# V1.net
KiCad netlist of a schematic drawn in Altium Designer
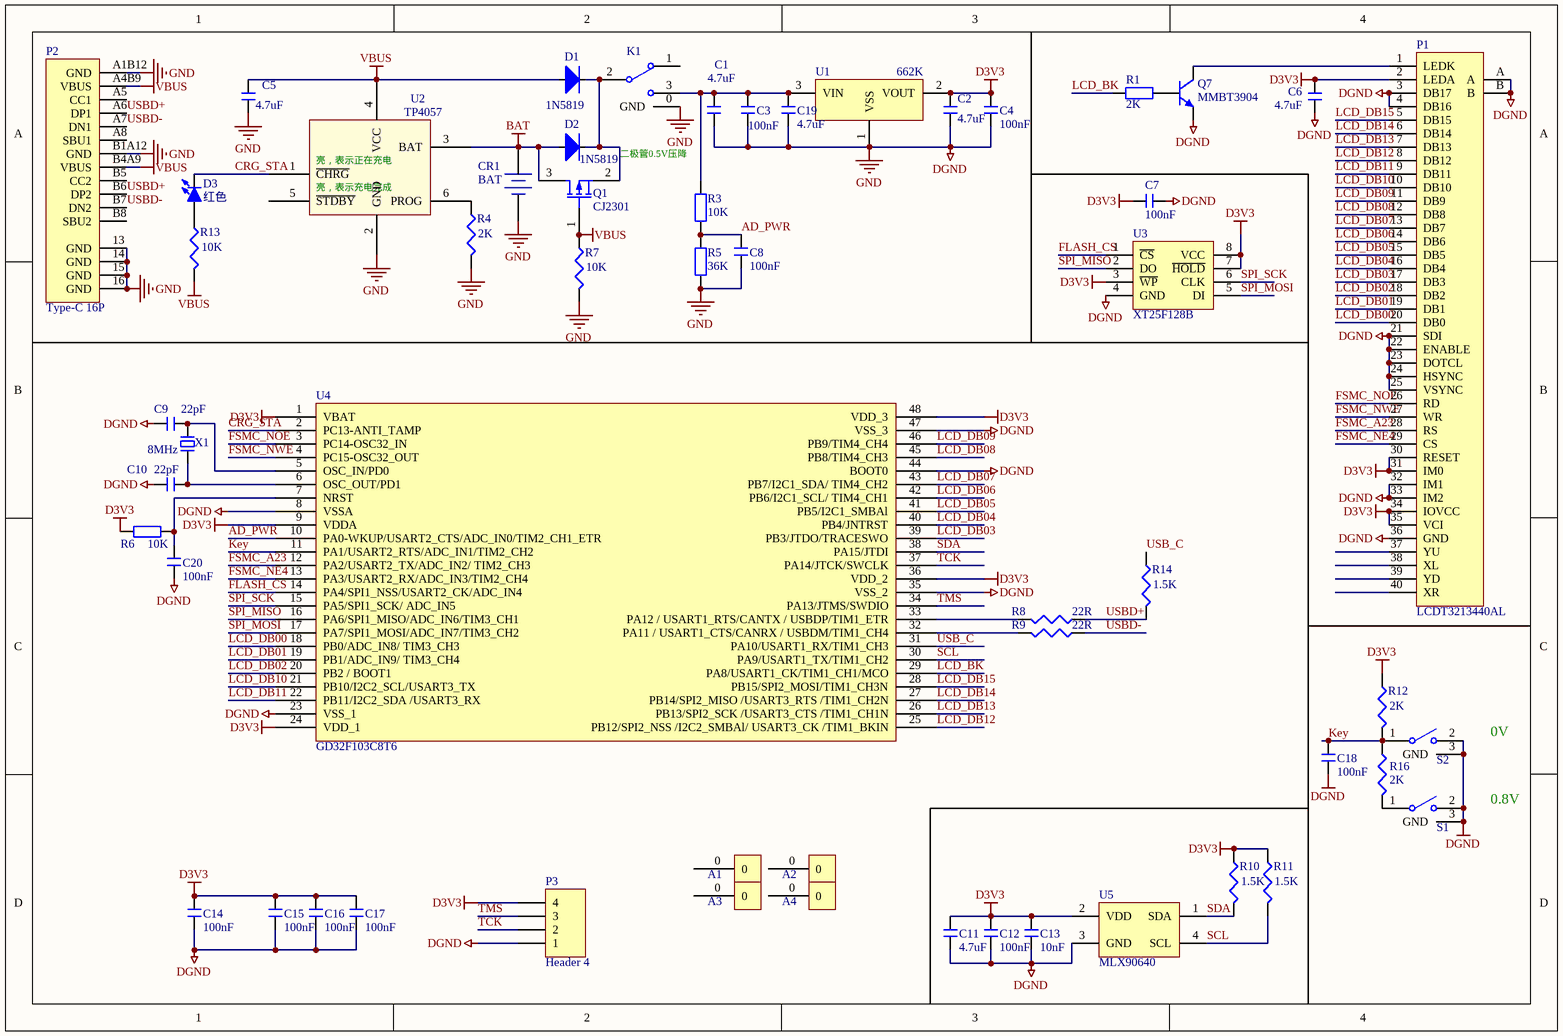
[diagram p0: 红外热成像V1.SchDoc]

(export (version "E")
  (design (tool "Eeschema 10.0.6"))
  (components
    (comp (ref "A1") (value "安装孔") (footprint "安装孔") (libsource (lib "standard") (part "安装孔")))
    (comp (ref "A2") (value "安装孔") (footprint "安装孔") (libsource (lib "standard") (part "安装孔")))
    (comp (ref "A3") (value "安装孔") (footprint "安装孔") (libsource (lib "standard") (part "安装孔")))
    (comp (ref "A4") (value "安装孔") (footprint "安装孔") (libsource (lib "standard") (part "安装孔")))
    (comp (ref "C1")
      (value "4.7uF")
      (footprint "C0603")
      (description "CAP")
      (fields (field (name "版权归属") "源创客"))
      (libsource (lib "3.1   - 电阻-电容-电感") (part "C"))
    )
    (comp (ref "C2")
      (value "4.7uF")
      (footprint "C0603")
      (description "CAP")
      (fields (field (name "版权归属") "源创客"))
      (libsource (lib "3.1   - 电阻-电容-电感") (part "C"))
    )
    (comp (ref "C3")
      (value "100nF")
      (footprint "C0603")
      (description "CAP")
      (fields (field (name "版权归属") "源创客"))
      (libsource (lib "3.1   - 电阻-电容-电感") (part "C"))
    )
    (comp (ref "C4")
      (value "100nF")
      (footprint "C0603")
      (description "CAP")
      (fields (field (name "版权归属") "源创客"))
      (libsource (lib "3.1   - 电阻-电容-电感") (part "C"))
    )
    (comp (ref "C5")
      (value "4.7uF")
      (footprint "C0603")
      (description "CAP")
      (fields (field (name "版权归属") "源创客"))
      (libsource (lib "3.1   - 电阻-电容-电感") (part "C"))
    )
    (comp (ref "C6")
      (value "4.7uF")
      (footprint "C0603")
      (description "CAP")
      (fields (field (name "版权归属") "源创客"))
      (libsource (lib "3.1   - 电阻-电容-电感") (part "C"))
    )
    (comp (ref "C7")
      (value "100nF")
      (footprint "C0603")
      (description "CAP")
      (fields (field (name "版权归属") "源创客"))
      (libsource (lib "3.1   - 电阻-电容-电感") (part "C"))
    )
    (comp (ref "C8")
      (value "100nF")
      (footprint "C0603")
      (description "CAP")
      (fields (field (name "版权归属") "源创客"))
      (libsource (lib "3.1   - 电阻-电容-电感") (part "C"))
    )
    (comp (ref "C9")
      (value "22pF")
      (footprint "C0603")
      (description "CAP")
      (fields (field (name "版权归属") "源创客"))
      (libsource (lib "3.1   - 电阻-电容-电感") (part "C"))
    )
    (comp (ref "C10")
      (value "22pF")
      (footprint "C0603")
      (description "CAP")
      (fields (field (name "版权归属") "源创客"))
      (libsource (lib "3.1   - 电阻-电容-电感") (part "C"))
    )
    (comp (ref "C11")
      (value "4.7uF")
      (footprint "C0603")
      (description "CAP")
      (fields (field (name "版权归属") "源创客"))
      (libsource (lib "3.1   - 电阻-电容-电感") (part "C"))
    )
    (comp (ref "C12")
      (value "100nF")
      (footprint "C0603")
      (description "CAP")
      (fields (field (name "版权归属") "源创客"))
      (libsource (lib "3.1   - 电阻-电容-电感") (part "C"))
    )
    (comp (ref "C13")
      (value "10nF")
      (footprint "C0603")
      (description "CAP")
      (fields (field (name "版权归属") "源创客"))
      (libsource (lib "3.1   - 电阻-电容-电感") (part "C"))
    )
    (comp (ref "C14")
      (value "100nF")
      (footprint "C0603")
      (description "CAP")
      (fields (field (name "版权归属") "源创客"))
      (libsource (lib "3.1   - 电阻-电容-电感") (part "C"))
    )
    (comp (ref "C15")
      (value "100nF")
      (footprint "C0603")
      (description "CAP")
      (fields (field (name "版权归属") "源创客"))
      (libsource (lib "3.1   - 电阻-电容-电感") (part "C"))
    )
    (comp (ref "C16")
      (value "100nF")
      (footprint "C0603")
      (description "CAP")
      (fields (field (name "版权归属") "源创客"))
      (libsource (lib "3.1   - 电阻-电容-电感") (part "C"))
    )
    (comp (ref "C17")
      (value "100nF")
      (footprint "C0603")
      (description "CAP")
      (fields (field (name "版权归属") "源创客"))
      (libsource (lib "3.1   - 电阻-电容-电感") (part "C"))
    )
    (comp (ref "C18")
      (value "100nF")
      (footprint "C0603")
      (description "CAP")
      (fields (field (name "版权归属") "源创客"))
      (libsource (lib "3.1   - 电阻-电容-电感") (part "C"))
    )
    (comp (ref "C19")
      (value "4.7uF")
      (footprint "C0603")
      (description "CAP")
      (fields (field (name "版权归属") "源创客"))
      (libsource (lib "3.1   - 电阻-电容-电感") (part "C"))
    )
    (comp (ref "C20")
      (value "100nF")
      (footprint "C0603")
      (description "CAP")
      (fields (field (name "版权归属") "源创客"))
      (libsource (lib "3.1   - 电阻-电容-电感") (part "C"))
    )
    (comp (ref "CR1")
      (value "BAT")
      (footprint "BAT")
      (description "锂电池")
      (fields (field (name "版权归属") "源创客"))
      (libsource (lib "未分类器件") (part "CR-3V"))
    )
    (comp (ref "D1")
      (value "1N5819")
      (footprint "SOD123")
      (description "二极管_整流")
      (fields (field (name "PUBLISHER") "Altium Limited"))
      (libsource (lib "*") (part "Diode"))
    )
    (comp (ref "D2")
      (value "1N5819")
      (footprint "SOD123")
      (description "二极管_整流")
      (fields (field (name "PUBLISHER") "Altium Limited"))
      (libsource (lib "*") (part "Diode"))
    )
    (comp (ref "D3")
      (value "红色")
      (footprint "D0805")
      (description "贴片LED")
      (fields (field (name "版权归属") "源创客"))
      (libsource (lib "9.1   - LED") (part "LED-SMD"))
    )
    (comp (ref "K1")
      (value "SS-12F23")
      (footprint "3P SW")
      (description "开关")
      (fields (field (name "版权归属") "源创客"))
      (libsource (lib "Schlib1") (part "SSW-1P"))
    )
    (comp (ref "P1")
      (value "LCDT3213440AL")
      (footprint "LCDT3213440AL")
      (description "接插件")
      (libsource (lib "Power_Show - V4") (part "LCDT3213440AL"))
    )
    (comp (ref "P2")
      (value "Type-C 16P")
      (footprint "Type-C 16P")
      (description "接插件")
      (libsource (lib "Schlib1") (part "Type-C 16P"))
    )
    (comp (ref "P3")
      (value "Header 4")
      (footprint "4PIN-1.27-STLink")
      (description "Header, 4-Pin")
      (fields (field (name "PUBLISHER") "Altium Limited"))
      (libsource (lib "Miscellaneous Connectors") (part "Header 4"))
    )
    (comp (ref "Q1")
      (value "CJ2301")
      (footprint "SOT-23")
      (description "MOS")
      (fields (field (name "PUBLISHER") "Altium Limited"))
      (libsource (lib "Miscellaneous Devices") (part "MOSFET-P"))
    )
    (comp (ref "Q7")
      (value "MMBT3904")
      (footprint "SOT23-3L")
      (description "三极管")
      (fields (field (name "版权归属") "源创客"))
      (libsource (lib "三极管") (part "9013-SMD"))
    )
    (comp (ref "R1")
      (value "2K")
      (footprint "R0603")
      (description "RES")
      (libsource (lib "standard") (part "RSSR0603"))
    )
    (comp (ref "R3")
      (value "10K")
      (footprint "R0603")
      (description "RES")
      (fields (field (name "版权归属") "源创客"))
      (libsource (lib "3.1   - 电阻-电容-电感") (part "R-Precision"))
    )
    (comp (ref "R4") (value "2K") (footprint "R0603") (description "RES") (libsource (lib "*") (part "RES")))
    (comp (ref "R5")
      (value "36K")
      (footprint "R0603")
      (description "RES")
      (fields (field (name "版权归属") "源创客"))
      (libsource (lib "3.1   - 电阻-电容-电感") (part "R-Precision"))
    )
    (comp (ref "R6")
      (value "10K")
      (footprint "R0603")
      (description "RES")
      (fields (field (name "版权归属") "源创客"))
      (libsource (lib "3.1   - 电阻-电容-电感") (part "R-Precision"))
    )
    (comp (ref "R7") (value "10K") (footprint "R0603") (description "RES") (libsource (lib "*") (part "RES")))
    (comp (ref "R8") (value "22R") (footprint "R0603") (description "RES") (libsource (lib "*") (part "RES")))
    (comp (ref "R9") (value "22R") (footprint "R0603") (description "RES") (libsource (lib "*") (part "RES")))
    (comp (ref "R10")
      (value "1.5K")
      (footprint "R0603")
      (description "RES")
      (libsource (lib "*") (part "RES"))
    )
    (comp (ref "R11")
      (value "1.5K")
      (footprint "R0603")
      (description "RES")
      (libsource (lib "*") (part "RES"))
    )
    (comp (ref "R12") (value "2K") (footprint "R0603") (description "RES") (libsource (lib "*") (part "RES")))
    (comp (ref "R13")
      (value "10K")
      (footprint "R0603")
      (description "RES")
      (libsource (lib "*") (part "RES"))
    )
    (comp (ref "R14")
      (value "1.5K")
      (footprint "R0603")
      (description "RES")
      (libsource (lib "*") (part "RES"))
    )
    (comp (ref "R16") (value "2K") (footprint "R0603") (description "RES") (libsource (lib "*") (part "RES")))
    (comp (ref "S1")
      (value "KCD1-101")
      (footprint "3P-Key")
      (description "按键")
      (fields (field (name "版权归属") "源创客"))
      (libsource (lib "Schlib1") (part "KCD1-101"))
    )
    (comp (ref "S2")
      (value "KCD1-101")
      (footprint "3P-Key")
      (description "按键")
      (fields (field (name "版权归属") "源创客"))
      (libsource (lib "Schlib1") (part "KCD1-101"))
    )
    (comp (ref "U1")
      (value "662K")
      (footprint "SOT-23")
      (description "芯片")
      (libsource (lib "Schlib1") (part "662K"))
    )
    (comp (ref "U2")
      (value "TP4057")
      (footprint "SOT23-6")
      (description "芯片")
      (libsource (lib "GBRL_Show") (part "Component_1"))
    )
    (comp (ref "U3")
      (value "XT25F128B")
      (footprint "SOP8W_N")
      (description "芯片")
      (fields (field (name "版权归属") "源创客"))
      (libsource (lib "IC芯片") (part "W25Qxx"))
    )
    (comp (ref "U4")
      (value "GD32F103C8T6")
      (footprint "LQFP_48")
      (description "芯片")
      (libsource (lib "*") (part "STM32F103CX"))
    )
    (comp (ref "U5")
      (value "MLX90640")
      (footprint "MLX90640")
      (description "芯片")
      (libsource (lib "Schlib1") (part "MLX90460"))
    )
    (comp (ref "X1")
      (value "8MHz")
      (footprint "XSR - duplicate")
      (description "晶振")
      (fields (field (name "版权归属") "源创客"))
      (libsource (lib "10.1 - 保险丝-晶振") (part "XTAL-2P"))
    )
  )
  (nets
    (net (code "1") (name "/AD_PWR") (class "Default")
      (node (ref "C8") (pin "2") (pinfunction "2_2") (pintype "passive"))
      (node (ref "R3") (pin "1") (pinfunction "1_1") (pintype "passive"))
      (node (ref "R5") (pin "2") (pinfunction "2_2") (pintype "passive"))
      (node (ref "U4") (pin "10") (pinfunction "PA0-WKUP/USART2_CTS/ADC_IN0/TIM2_CH1_ETR_10") (pintype "passive"))
    )
    (net (code "2") (name "/CRG_STA") (class "Default")
      (node (ref "D3") (pin "2") (pinfunction "K_2") (pintype "passive"))
      (node (ref "U2") (pin "1") (pinfunction "~{CHRG}_1") (pintype "passive"))
      (node (ref "U4") (pin "2") (pinfunction "PC13-ANTI_TAMP_2") (pintype "passive"))
    )
    (net (code "3") (name "/FLASH_CS") (class "Default")
      (node (ref "U3") (pin "1") (pinfunction "~{CS}_1") (pintype "passive"))
      (node (ref "U4") (pin "14") (pinfunction "PA4/SPI1_NSS/USART2_CK/ADC_IN4_14") (pintype "passive"))
    )
    (net (code "4") (name "/FSMC_A23") (class "Default")
      (node (ref "P1") (pin "28") (pinfunction "RS_28") (pintype "passive"))
      (node (ref "U4") (pin "12") (pinfunction "PA2/USART2_TX/ADC_IN2/_TIM2_CH3_12") (pintype "passive"))
    )
    (net (code "5") (name "/FSMC_NE4") (class "Default")
      (node (ref "P1") (pin "29") (pinfunction "CS_29") (pintype "passive"))
      (node (ref "U4") (pin "13") (pinfunction "PA3/USART2_RX/ADC_IN3/TIM2_CH4_13") (pintype "passive"))
    )
    (net (code "6") (name "/FSMC_NOE") (class "Default")
      (node (ref "P1") (pin "26") (pinfunction "RD_26") (pintype "passive"))
      (node (ref "U4") (pin "3") (pinfunction "PC14-OSC32_IN_3") (pintype "passive"))
    )
    (net (code "7") (name "/FSMC_NWE") (class "Default")
      (node (ref "P1") (pin "27") (pinfunction "WR_27") (pintype "passive"))
      (node (ref "U4") (pin "4") (pinfunction "PC15-OSC32_OUT_4") (pintype "passive"))
    )
    (net (code "8") (name "/Key") (class "Default")
      (node (ref "C18") (pin "2") (pinfunction "2_2") (pintype "passive"))
      (node (ref "R12") (pin "1") (pintype "passive"))
      (node (ref "R16") (pin "2") (pintype "passive"))
      (node (ref "S2") (pin "1") (pinfunction "1_1") (pintype "passive"))
      (node (ref "U4") (pin "11") (pinfunction "PA1/USART2_RTS/ADC_IN1/TIM2_CH2_11") (pintype "passive"))
    )
    (net (code "9") (name "/LCD_BK") (class "Default")
      (node (ref "R1") (pin "2") (pinfunction "2_2") (pintype "passive"))
      (node (ref "U4") (pin "29") (pinfunction "PA8/USART1_CK/TIM1_CH1/MCO_29") (pintype "passive"))
    )
    (net (code "10") (name "/LCD_DB00") (class "Default")
      (node (ref "P1") (pin "20") (pinfunction "DB0_20") (pintype "passive"))
      (node (ref "U4") (pin "18") (pinfunction "PB0/ADC_IN8/_TIM3_CH3_18") (pintype "passive"))
    )
    (net (code "11") (name "/LCD_DB01") (class "Default")
      (node (ref "P1") (pin "19") (pinfunction "DB1_19") (pintype "passive"))
      (node (ref "U4") (pin "19") (pinfunction "PB1/ADC_IN9/_TIM3_CH4_19") (pintype "passive"))
    )
    (net (code "12") (name "/LCD_DB02") (class "Default")
      (node (ref "P1") (pin "18") (pinfunction "DB2_18") (pintype "passive"))
      (node (ref "U4") (pin "20") (pinfunction "PB2_/_BOOT1_20") (pintype "passive"))
    )
    (net (code "13") (name "/LCD_DB03") (class "Default")
      (node (ref "P1") (pin "17") (pinfunction "DB3_17") (pintype "passive"))
      (node (ref "U4") (pin "39") (pinfunction "PB3/JTDO/TRACESWO_39") (pintype "passive"))
    )
    (net (code "14") (name "/LCD_DB04") (class "Default")
      (node (ref "P1") (pin "16") (pinfunction "DB4_16") (pintype "passive"))
      (node (ref "U4") (pin "40") (pinfunction "PB4/JNTRST_40") (pintype "passive"))
    )
    (net (code "15") (name "/LCD_DB05") (class "Default")
      (node (ref "P1") (pin "15") (pinfunction "DB5_15") (pintype "passive"))
      (node (ref "U4") (pin "41") (pinfunction "PB5/I2C1_SMBAl_41") (pintype "passive"))
    )
    (net (code "16") (name "/LCD_DB06") (class "Default")
      (node (ref "P1") (pin "14") (pinfunction "DB6_14") (pintype "passive"))
      (node (ref "U4") (pin "42") (pinfunction "PB6/I2C1_SCL/_TIM4_CH1_42") (pintype "passive"))
    )
    (net (code "17") (name "/LCD_DB07") (class "Default")
      (node (ref "P1") (pin "13") (pinfunction "DB7_13") (pintype "passive"))
      (node (ref "U4") (pin "43") (pinfunction "PB7/I2C1_SDA/_TIM4_CH2_43") (pintype "passive"))
    )
    (net (code "18") (name "/LCD_DB08") (class "Default")
      (node (ref "P1") (pin "12") (pinfunction "DB8_12") (pintype "passive"))
      (node (ref "U4") (pin "45") (pinfunction "PB8/TIM4_CH3_45") (pintype "passive"))
    )
    (net (code "19") (name "/LCD_DB09") (class "Default")
      (node (ref "P1") (pin "11") (pinfunction "DB9_11") (pintype "passive"))
      (node (ref "U4") (pin "46") (pinfunction "PB9/TIM4_CH4_46") (pintype "passive"))
    )
    (net (code "20") (name "/LCD_DB10") (class "Default")
      (node (ref "P1") (pin "10") (pinfunction "DB10_10") (pintype "passive"))
      (node (ref "U4") (pin "21") (pinfunction "PB10/I2C2_SCL/USART3_TX_21") (pintype "passive"))
    )
    (net (code "21") (name "/LCD_DB11") (class "Default")
      (node (ref "P1") (pin "9") (pinfunction "DB11_9") (pintype "passive"))
      (node (ref "U4") (pin "22") (pinfunction "PB11/I2C2_SDA_/USART3_RX_22") (pintype "passive"))
    )
    (net (code "22") (name "/LCD_DB12") (class "Default")
      (node (ref "P1") (pin "8") (pinfunction "DB12_8") (pintype "passive"))
      (node (ref "U4") (pin "25") (pinfunction "PB12/SPI2_NSS_/I2C2_SMBAl/_USART3_CK_/TIM1_BKIN_25") (pintype "passive"))
    )
    (net (code "23") (name "/LCD_DB13") (class "Default")
      (node (ref "P1") (pin "7") (pinfunction "DB13_7") (pintype "passive"))
      (node (ref "U4") (pin "26") (pinfunction "PB13/SPI2_SCK_/USART3_CTS_/TIM1_CH1N_26") (pintype "passive"))
    )
    (net (code "24") (name "/LCD_DB14") (class "Default")
      (node (ref "P1") (pin "6") (pinfunction "DB14_6") (pintype "passive"))
      (node (ref "U4") (pin "27") (pinfunction "PB14/SPI2_MISO_/USART3_RTS_/TIM1_CH2N_27") (pintype "passive"))
    )
    (net (code "25") (name "/LCD_DB15") (class "Default")
      (node (ref "P1") (pin "5") (pinfunction "DB15_5") (pintype "passive"))
      (node (ref "U4") (pin "28") (pinfunction "PB15/SPI2_MOSI/TIM1_CH3N_28") (pintype "passive"))
    )
    (net (code "26") (name "/SCL") (class "Default")
      (node (ref "R11") (pin "1") (pintype "passive"))
      (node (ref "U4") (pin "30") (pinfunction "PA9/USART1_TX/TIM1_CH2_30") (pintype "passive"))
      (node (ref "U5") (pin "4") (pinfunction "SCL_4") (pintype "passive"))
    )
    (net (code "27") (name "/SDA") (class "Default")
      (node (ref "R10") (pin "1") (pintype "passive"))
      (node (ref "U4") (pin "38") (pinfunction "PA15/JTDI_38") (pintype "passive"))
      (node (ref "U5") (pin "1") (pinfunction "SDA_1") (pintype "passive"))
    )
    (net (code "28") (name "/SPI_MISO") (class "Default")
      (node (ref "U3") (pin "2") (pinfunction "DO_2") (pintype "passive"))
      (node (ref "U4") (pin "16") (pinfunction "PA6/SPI1_MISO/ADC_IN6/TIM3_CH1_16") (pintype "passive"))
    )
    (net (code "29") (name "/SPI_MOSI") (class "Default")
      (node (ref "U3") (pin "5") (pinfunction "DI_5") (pintype "passive"))
      (node (ref "U4") (pin "17") (pinfunction "PA7/SPI1_MOSI/ADC_IN7/TIM3_CH2_17") (pintype "passive"))
    )
    (net (code "30") (name "/SPI_SCK") (class "Default")
      (node (ref "U3") (pin "6") (pinfunction "CLK_6") (pintype "passive"))
      (node (ref "U4") (pin "15") (pinfunction "PA5/SPI1_SCK/_ADC_IN5_15") (pintype "passive"))
    )
    (net (code "31") (name "/TCK") (class "Default")
      (node (ref "P3") (pin "2") (pinfunction "2_2") (pintype "passive"))
      (node (ref "U4") (pin "37") (pinfunction "PA14/JTCK/SWCLK_37") (pintype "passive"))
    )
    (net (code "32") (name "/TMS") (class "Default")
      (node (ref "P3") (pin "3") (pinfunction "3_3") (pintype "passive"))
      (node (ref "U4") (pin "34") (pinfunction "PA13/JTMS/SWDIO_34") (pintype "passive"))
    )
    (net (code "33") (name "/USBD+") (class "Default")
      (node (ref "P2") (pin "A6") (pinfunction "DP1_A6") (pintype "passive"))
      (node (ref "P2") (pin "B6") (pinfunction "DP2_B6") (pintype "passive"))
      (node (ref "R14") (pin "1") (pintype "passive"))
      (node (ref "R8") (pin "2") (pintype "passive"))
    )
    (net (code "34") (name "/USBD-") (class "Default")
      (node (ref "P2") (pin "A7") (pinfunction "DN1_A7") (pintype "passive"))
      (node (ref "P2") (pin "B7") (pinfunction "DN2_B7") (pintype "passive"))
      (node (ref "R9") (pin "2") (pintype "passive"))
    )
    (net (code "35") (name "/USB_C") (class "Default")
      (node (ref "R14") (pin "2") (pintype "passive"))
      (node (ref "U4") (pin "31") (pinfunction "PA10/USART1_RX/TIM1_CH3_31") (pintype "passive"))
    )
    (net (code "36") (name "BAT") (class "Default")
      (node (ref "CR1") (pin "1") (pinfunction "DC+_1") (pintype "passive"))
      (node (ref "D2") (pin "1") (pinfunction "A_1") (pintype "passive"))
      (node (ref "Q1") (pin "3") (pinfunction "D_3") (pintype "passive"))
      (node (ref "U2") (pin "3") (pinfunction "BAT_3") (pintype "passive"))
    )
    (net (code "37") (name "D3V3") (class "Default")
      (node (ref "C11") (pin "1") (pinfunction "1_1") (pintype "passive"))
      (node (ref "C12") (pin "2") (pinfunction "2_2") (pintype "passive"))
      (node (ref "C13") (pin "2") (pinfunction "2_2") (pintype "passive"))
      (node (ref "C14") (pin "2") (pinfunction "2_2") (pintype "passive"))
      (node (ref "C15") (pin "2") (pinfunction "2_2") (pintype "passive"))
      (node (ref "C16") (pin "2") (pinfunction "2_2") (pintype "passive"))
      (node (ref "C17") (pin "2") (pinfunction "2_2") (pintype "passive"))
      (node (ref "C2") (pin "1") (pinfunction "1_1") (pintype "passive"))
      (node (ref "C4") (pin "2") (pinfunction "2_2") (pintype "passive"))
      (node (ref "C6") (pin "2") (pinfunction "2_2") (pintype "passive"))
      (node (ref "C7") (pin "2") (pinfunction "2_2") (pintype "passive"))
      (node (ref "P1") (pin "2") (pinfunction "LEDA_2") (pintype "passive"))
      (node (ref "P1") (pin "30") (pinfunction "RESET_30") (pintype "passive"))
      (node (ref "P1") (pin "31") (pinfunction "IM0_31") (pintype "passive"))
      (node (ref "P1") (pin "34") (pinfunction "IOVCC_34") (pintype "passive"))
      (node (ref "P1") (pin "35") (pinfunction "VCI_35") (pintype "passive"))
      (node (ref "P3") (pin "4") (pinfunction "4_4") (pintype "passive"))
      (node (ref "R10") (pin "2") (pintype "passive"))
      (node (ref "R11") (pin "2") (pintype "passive"))
      (node (ref "R12") (pin "2") (pintype "passive"))
      (node (ref "R6") (pin "2") (pinfunction "2_2") (pintype "passive"))
      (node (ref "U1") (pin "2") (pinfunction "VOUT_2") (pintype "passive"))
      (node (ref "U3") (pin "3") (pinfunction "~{WP}_3") (pintype "passive"))
      (node (ref "U3") (pin "7") (pinfunction "~{HOLD}_7") (pintype "passive"))
      (node (ref "U3") (pin "8") (pinfunction "VCC_8") (pintype "passive"))
      (node (ref "U4") (pin "1") (pinfunction "VBAT_1") (pintype "passive"))
      (node (ref "U4") (pin "24") (pinfunction "VDD_1_24") (pintype "passive"))
      (node (ref "U4") (pin "36") (pinfunction "VDD_2_36") (pintype "passive"))
      (node (ref "U4") (pin "48") (pinfunction "VDD_3_48") (pintype "passive"))
      (node (ref "U4") (pin "9") (pinfunction "VDDA_9") (pintype "passive"))
      (node (ref "U5") (pin "2") (pinfunction "VDD_2") (pintype "passive"))
    )
    (net (code "38") (name "DGND") (class "Default")
      (node (ref "C1") (pin "2") (pinfunction "2_2") (pintype "passive"))
      (node (ref "C10") (pin "1") (pinfunction "1_1") (pintype "passive"))
      (node (ref "C11") (pin "2") (pinfunction "2_2") (pintype "passive"))
      (node (ref "C12") (pin "1") (pinfunction "1_1") (pintype "passive"))
      (node (ref "C13") (pin "1") (pinfunction "1_1") (pintype "passive"))
      (node (ref "C14") (pin "1") (pinfunction "1_1") (pintype "passive"))
      (node (ref "C15") (pin "1") (pinfunction "1_1") (pintype "passive"))
      (node (ref "C16") (pin "1") (pinfunction "1_1") (pintype "passive"))
      (node (ref "C17") (pin "1") (pinfunction "1_1") (pintype "passive"))
      (node (ref "C18") (pin "1") (pinfunction "1_1") (pintype "passive"))
      (node (ref "C19") (pin "1") (pinfunction "1_1") (pintype "passive"))
      (node (ref "C2") (pin "2") (pinfunction "2_2") (pintype "passive"))
      (node (ref "C20") (pin "2") (pinfunction "2_2") (pintype "passive"))
      (node (ref "C3") (pin "1") (pinfunction "1_1") (pintype "passive"))
      (node (ref "C4") (pin "1") (pinfunction "1_1") (pintype "passive"))
      (node (ref "C5") (pin "2") (pinfunction "2_2") (pintype "passive"))
      (node (ref "C6") (pin "1") (pinfunction "1_1") (pintype "passive"))
      (node (ref "C7") (pin "1") (pinfunction "1_1") (pintype "passive"))
      (node (ref "C8") (pin "1") (pinfunction "1_1") (pintype "passive"))
      (node (ref "C9") (pin "1") (pinfunction "1_1") (pintype "passive"))
      (node (ref "CR1") (pin "2") (pinfunction "DC-_2") (pintype "passive"))
      (node (ref "K1") (pin "0") (pinfunction "GND_0") (pintype "passive"))
      (node (ref "P1") (pin "21") (pinfunction "SDI_21") (pintype "passive"))
      (node (ref "P1") (pin "22") (pinfunction "ENABLE_22") (pintype "passive"))
      (node (ref "P1") (pin "23") (pinfunction "DOTCL_23") (pintype "passive"))
      (node (ref "P1") (pin "24") (pinfunction "HSYNC_24") (pintype "passive"))
      (node (ref "P1") (pin "25") (pinfunction "VSYNC_25") (pintype "passive"))
      (node (ref "P1") (pin "3") (pinfunction "DB17_3") (pintype "passive"))
      (node (ref "P1") (pin "32") (pinfunction "IM1_32") (pintype "passive"))
      (node (ref "P1") (pin "33") (pinfunction "IM2_33") (pintype "passive"))
      (node (ref "P1") (pin "36") (pinfunction "GND_36") (pintype "passive"))
      (node (ref "P1") (pin "4") (pinfunction "DB16_4") (pintype "passive"))
      (node (ref "P1") (pin "A") (pinfunction "A_A") (pintype "passive"))
      (node (ref "P1") (pin "B") (pinfunction "B_B") (pintype "passive"))
      (node (ref "P2") (pin "13") (pinfunction "GND_13") (pintype "passive"))
      (node (ref "P2") (pin "14") (pinfunction "GND_14") (pintype "passive"))
      (node (ref "P2") (pin "15") (pinfunction "GND_15") (pintype "passive"))
      (node (ref "P2") (pin "16") (pinfunction "GND_16") (pintype "passive"))
      (node (ref "P2") (pin "A1B12") (pinfunction "GND_A1B12") (pintype "passive"))
      (node (ref "P2") (pin "B1A12") (pinfunction "GND_B1A12") (pintype "passive"))
      (node (ref "P3") (pin "1") (pinfunction "1_1") (pintype "passive"))
      (node (ref "Q7") (pin "2") (pinfunction "E_2") (pintype "passive"))
      (node (ref "R4") (pin "1") (pintype "passive"))
      (node (ref "R5") (pin "1") (pinfunction "1_1") (pintype "passive"))
      (node (ref "R7") (pin "1") (pintype "passive"))
      (node (ref "S1") (pin "2") (pinfunction "2_2") (pintype "passive"))
      (node (ref "S1") (pin "3") (pinfunction "GND_3") (pintype "passive"))
      (node (ref "S2") (pin "2") (pinfunction "2_2") (pintype "passive"))
      (node (ref "S2") (pin "3") (pinfunction "GND_3") (pintype "passive"))
      (node (ref "U1") (pin "1") (pinfunction "VSS_1") (pintype "passive"))
      (node (ref "U2") (pin "2") (pinfunction "GND_2") (pintype "passive"))
      (node (ref "U3") (pin "4") (pinfunction "GND_4") (pintype "passive"))
      (node (ref "U4") (pin "23") (pinfunction "VSS_1_23") (pintype "passive"))
      (node (ref "U4") (pin "35") (pinfunction "VSS_2_35") (pintype "passive"))
      (node (ref "U4") (pin "44") (pinfunction "BOOT0_44") (pintype "passive"))
      (node (ref "U4") (pin "47") (pinfunction "VSS_3_47") (pintype "passive"))
      (node (ref "U4") (pin "8") (pinfunction "VSSA_8") (pintype "passive"))
      (node (ref "U5") (pin "3") (pinfunction "GND_3") (pintype "passive"))
    )
    (net (code "39") (name "Net-(D1-K)") (class "Default")
      (node (ref "D1") (pin "2") (pinfunction "K_2") (pintype "passive"))
      (node (ref "D2") (pin "2") (pinfunction "K_2") (pintype "passive"))
      (node (ref "K1") (pin "2") (pinfunction "2_2") (pintype "passive"))
      (node (ref "Q1") (pin "2") (pinfunction "S_2") (pintype "passive"))
    )
    (net (code "40") (name "Net-(D3-A)") (class "Default")
      (node (ref "D3") (pin "1") (pinfunction "A_1") (pintype "passive"))
      (node (ref "R13") (pin "2") (pintype "passive"))
    )
    (net (code "41") (name "Net-(P1-LEDK)") (class "Default")
      (node (ref "P1") (pin "1") (pinfunction "LEDK_1") (pintype "passive"))
      (node (ref "Q7") (pin "3") (pinfunction "C_3") (pintype "passive"))
    )
    (net (code "42") (name "Net-(Q7-B)") (class "Default")
      (node (ref "Q7") (pin "1") (pinfunction "B_1") (pintype "passive"))
      (node (ref "R1") (pin "1") (pinfunction "1_1") (pintype "passive"))
    )
    (net (code "43") (name "Net-(R16-Pad1)") (class "Default")
      (node (ref "R16") (pin "1") (pintype "passive"))
      (node (ref "S1") (pin "1") (pinfunction "1_1") (pintype "passive"))
    )
    (net (code "44") (name "Net-(U1-VIN)") (class "Default")
      (node (ref "C1") (pin "1") (pinfunction "1_1") (pintype "passive"))
      (node (ref "C19") (pin "2") (pinfunction "2_2") (pintype "passive"))
      (node (ref "C3") (pin "2") (pinfunction "2_2") (pintype "passive"))
      (node (ref "K1") (pin "3") (pinfunction "3_3") (pintype "passive"))
      (node (ref "R3") (pin "2") (pinfunction "2_2") (pintype "passive"))
      (node (ref "U1") (pin "3") (pinfunction "VIN_3") (pintype "passive"))
    )
    (net (code "45") (name "Net-(U2-PROG)") (class "Default")
      (node (ref "R4") (pin "2") (pintype "passive"))
      (node (ref "U2") (pin "6") (pinfunction "PROG_6") (pintype "passive"))
    )
    (net (code "46") (name "Net-(U4-NRST)") (class "Default")
      (node (ref "C20") (pin "1") (pinfunction "1_1") (pintype "passive"))
      (node (ref "R6") (pin "1") (pinfunction "1_1") (pintype "passive"))
      (node (ref "U4") (pin "7") (pinfunction "NRST_7") (pintype "passive"))
    )
    (net (code "47") (name "Net-(U4-OSC_IN{slash}PD0)") (class "Default")
      (node (ref "C9") (pin "2") (pinfunction "2_2") (pintype "passive"))
      (node (ref "U4") (pin "5") (pinfunction "OSC_IN/PD0_5") (pintype "passive"))
      (node (ref "X1") (pin "1") (pinfunction "1_1") (pintype "passive"))
    )
    (net (code "48") (name "Net-(U4-OSC_OUT{slash}PD1)") (class "Default")
      (node (ref "C10") (pin "2") (pinfunction "2_2") (pintype "passive"))
      (node (ref "U4") (pin "6") (pinfunction "OSC_OUT/PD1_6") (pintype "passive"))
      (node (ref "X1") (pin "2") (pinfunction "2_2") (pintype "passive"))
    )
    (net (code "49") (name "Net-(U4-PA11_{slash}_USART1_CTS{slash}CANRX_{slash}_USBDM{slash}TIM1_CH4)") (class "Default")
      (node (ref "R9") (pin "1") (pintype "passive"))
      (node (ref "U4") (pin "32") (pinfunction "PA11_/_USART1_CTS/CANRX_/_USBDM/TIM1_CH4_32") (pintype "passive"))
    )
    (net (code "50") (name "Net-(U4-PA12_{slash}_USART1_RTS{slash}CANTX_{slash}_USBDP{slash}TIM1_ETR)") (class "Default")
      (node (ref "R8") (pin "1") (pintype "passive"))
      (node (ref "U4") (pin "33") (pinfunction "PA12_/_USART1_RTS/CANTX_/_USBDP/TIM1_ETR_33") (pintype "passive"))
    )
    (net (code "51") (name "VBUS") (class "Default")
      (node (ref "C5") (pin "1") (pinfunction "1_1") (pintype "passive"))
      (node (ref "D1") (pin "1") (pinfunction "A_1") (pintype "passive"))
      (node (ref "P2") (pin "A4B9") (pinfunction "VBUS_A4B9") (pintype "passive"))
      (node (ref "P2") (pin "B4A9") (pinfunction "VBUS_B4A9") (pintype "passive"))
      (node (ref "Q1") (pin "1") (pinfunction "G_1") (pintype "passive"))
      (node (ref "R13") (pin "1") (pintype "passive"))
      (node (ref "R7") (pin "2") (pintype "passive"))
      (node (ref "U2") (pin "4") (pinfunction "VCC_4") (pintype "passive"))
    )
    (net (code "52") (name "unconnected-(A1-Pad0)") (class "Default")
      (node (ref "A1") (pin "0") (pinfunction "0_0") (pintype "passive"))
    )
    (net (code "53") (name "unconnected-(A2-Pad0)") (class "Default")
      (node (ref "A2") (pin "0") (pinfunction "0_0") (pintype "passive"))
    )
    (net (code "54") (name "unconnected-(A3-Pad0)") (class "Default")
      (node (ref "A3") (pin "0") (pinfunction "0_0") (pintype "passive"))
    )
    (net (code "55") (name "unconnected-(A4-Pad0)") (class "Default")
      (node (ref "A4") (pin "0") (pinfunction "0_0") (pintype "passive"))
    )
    (net (code "56") (name "unconnected-(K1-Pad1)") (class "Default")
      (node (ref "K1") (pin "1") (pinfunction "1_1") (pintype "passive"))
    )
    (net (code "57") (name "unconnected-(P1-XL-Pad38)") (class "Default")
      (node (ref "P1") (pin "38") (pinfunction "XL_38") (pintype "passive"))
    )
    (net (code "58") (name "unconnected-(P1-XR-Pad40)") (class "Default")
      (node (ref "P1") (pin "40") (pinfunction "XR_40") (pintype "passive"))
    )
    (net (code "59") (name "unconnected-(P1-YD-Pad39)") (class "Default")
      (node (ref "P1") (pin "39") (pinfunction "YD_39") (pintype "passive"))
    )
    (net (code "60") (name "unconnected-(P1-YU-Pad37)") (class "Default")
      (node (ref "P1") (pin "37") (pinfunction "YU_37") (pintype "passive"))
    )
    (net (code "61") (name "unconnected-(P2-CC1-PadA5)") (class "Default")
      (node (ref "P2") (pin "A5") (pinfunction "CC1_A5") (pintype "passive"))
    )
    (net (code "62") (name "unconnected-(P2-CC2-PadB5)") (class "Default")
      (node (ref "P2") (pin "B5") (pinfunction "CC2_B5") (pintype "passive"))
    )
    (net (code "63") (name "unconnected-(P2-SBU1-PadA8)") (class "Default")
      (node (ref "P2") (pin "A8") (pinfunction "SBU1_A8") (pintype "passive"))
    )
    (net (code "64") (name "unconnected-(P2-SBU2-PadB8)") (class "Default")
      (node (ref "P2") (pin "B8") (pinfunction "SBU2_B8") (pintype "passive"))
    )
    (net (code "65") (name "unconnected-(U2-~{STDBY}-Pad5)") (class "Default")
      (node (ref "U2") (pin "5") (pinfunction "~{STDBY}_5") (pintype "passive"))
    )
  )
)
